# rev3_01.net
KiCad netlist of a schematic drawn in EAGLE
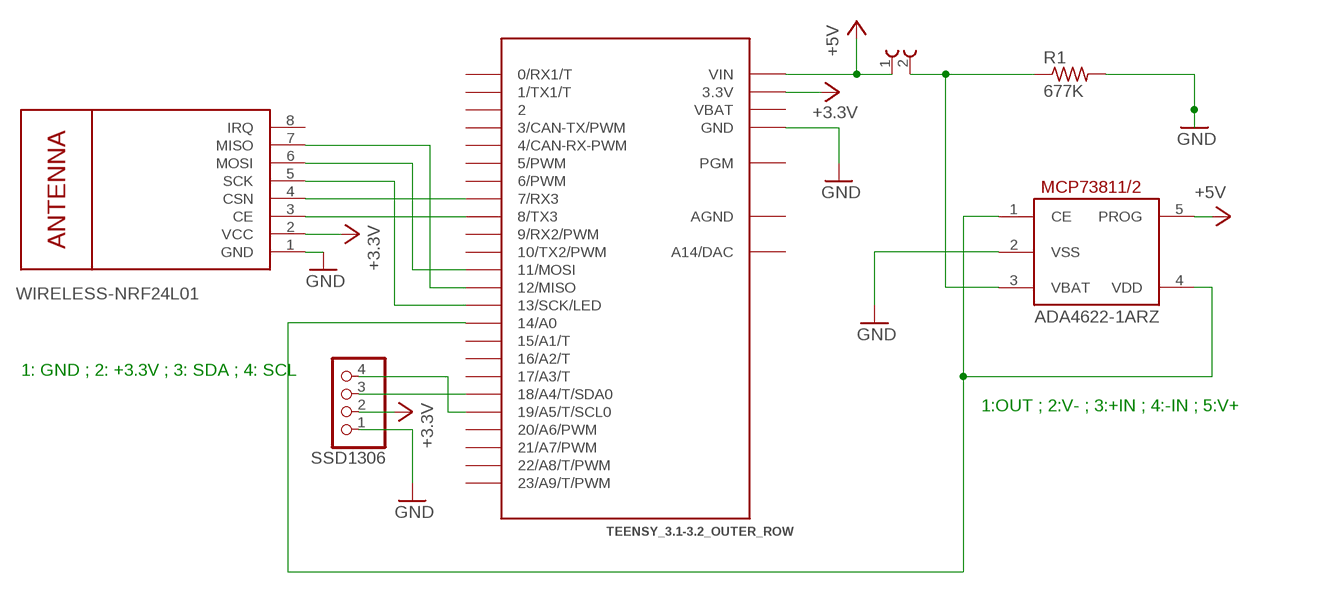
[diagram p0: schematic, sheet 1]

(export (version "E")
  (design (tool "Eeschema 10.0.6"))
  (components
    (comp (ref "ADA4622-1ARZ")
      (value "MCP73811/2")
      (footprint "eagle-import:SOT23-5L")
      (libsource (lib "eagle-import") (part "MCP73811/2"))
    )
    (comp (ref "M1")
      (value "WIRELESS-NRF24L01")
      (footprint "eagle-import:WIRELESS-NRF24L01")
      (libsource (lib "eagle-import") (part "WIRELESS-NRF24L01"))
    )
    (comp (ref "R1")
      (value "677K")
      (footprint "eagle-import:R0805W")
      (libsource (lib "eagle-import") (part "R-US_R0805W"))
    )
    (comp (ref "R_MES")
      (value "691214310002")
      (footprint "eagle-import:691214310002")
      (libsource (lib "eagle-import") (part "691214310002"))
    )
    (comp (ref "SSD1306")
      (value "PINHD-1X4")
      (footprint "eagle-import:1X04")
      (libsource (lib "eagle-import") (part "PINHD-1X4"))
    )
    (comp (ref "U$2")
      (value "TEENSY_3.1-3.2_OUTER_ROW")
      (footprint "eagle-import:TEENSY_3.0-3.2&LC_OUTER_ROW")
      (libsource (lib "eagle-import") (part "TEENSY_3.1-3.2_OUTER_ROW"))
    )
  )
  (nets
    (net (code "1") (name "+3.3V") (class "Default")
      (node (ref "M1") (pin "2") (pinfunction "VCC_2") (pintype "power_in"))
      (node (ref "SSD1306") (pin "2") (pinfunction "2_2") (pintype "passive"))
      (node (ref "U$2") (pin "3.3V") (pinfunction "3.3V_3.3V") (pintype "power_in"))
      (node (ref "U$2") (pin "3.3V1") (pinfunction "3.3V_3.3V1") (pintype "power_in"))
    )
    (net (code "2") (name "+5V") (class "Default")
      (node (ref "ADA4622-1ARZ") (pin "5") (pinfunction "PROG_5") (pintype "input"))
      (node (ref "R_MES") (pin "1") (pinfunction "1_1") (pintype "passive"))
      (node (ref "U$2") (pin "VIN") (pinfunction "VIN_VIN") (pintype "power_in"))
    )
    (net (code "3") (name "/AGND") (class "Default")
      (node (ref "U$2") (pin "AGND") (pinfunction "AGND_AGND") (pintype "power_in"))
    )
    (net (code "4") (name "/VBAT") (class "Default")
      (node (ref "U$2") (pin "VBAT") (pinfunction "VBAT_VBAT") (pintype "power_in"))
    )
    (net (code "5") (name "GND") (class "Default")
      (node (ref "ADA4622-1ARZ") (pin "2") (pinfunction "VSS_2") (pintype "power_in"))
      (node (ref "M1") (pin "1") (pinfunction "GND_1") (pintype "power_in"))
      (node (ref "R1") (pin "2") (pinfunction "2_2") (pintype "passive"))
      (node (ref "SSD1306") (pin "1") (pinfunction "1_1") (pintype "passive"))
      (node (ref "U$2") (pin "GND") (pinfunction "GND_GND") (pintype "power_in"))
      (node (ref "U$2") (pin "GND1") (pinfunction "GND_GND1") (pintype "power_in"))
    )
    (net (code "6") (name "Net-(ADA4622-1ARZ-CE)") (class "Default")
      (node (ref "ADA4622-1ARZ") (pin "1") (pinfunction "CE_1") (pintype "input"))
      (node (ref "ADA4622-1ARZ") (pin "4") (pinfunction "VDD_4") (pintype "power_in"))
      (node (ref "U$2") (pin "14/A0") (pinfunction "14/A0_14/A0") (pintype "bidirectional"))
    )
    (net (code "7") (name "Net-(ADA4622-1ARZ-VBAT)") (class "Default")
      (node (ref "ADA4622-1ARZ") (pin "3") (pinfunction "VBAT_3") (pintype "bidirectional"))
      (node (ref "R1") (pin "1") (pinfunction "1_1") (pintype "passive"))
      (node (ref "R_MES") (pin "2") (pinfunction "2_2") (pintype "passive"))
    )
    (net (code "8") (name "Net-(M1-CE)") (class "Default")
      (node (ref "M1") (pin "3") (pinfunction "CE_3") (pintype "bidirectional"))
      (node (ref "U$2") (pin "8") (pinfunction "8/TX3_8") (pintype "bidirectional"))
    )
    (net (code "9") (name "Net-(M1-CSN)") (class "Default")
      (node (ref "M1") (pin "4") (pinfunction "CSN_4") (pintype "bidirectional"))
      (node (ref "U$2") (pin "7") (pinfunction "7/RX3_7") (pintype "bidirectional"))
    )
    (net (code "10") (name "Net-(M1-MISO)") (class "Default")
      (node (ref "M1") (pin "7") (pinfunction "MISO_7") (pintype "bidirectional"))
      (node (ref "U$2") (pin "12") (pinfunction "12/MISO_12") (pintype "bidirectional"))
    )
    (net (code "11") (name "Net-(M1-MOSI)") (class "Default")
      (node (ref "M1") (pin "6") (pinfunction "MOSI_6") (pintype "bidirectional"))
      (node (ref "U$2") (pin "11") (pinfunction "11/MOSI_11") (pintype "bidirectional"))
    )
    (net (code "12") (name "Net-(M1-SCK)") (class "Default")
      (node (ref "M1") (pin "5") (pinfunction "SCK_5") (pintype "bidirectional"))
      (node (ref "U$2") (pin "13") (pinfunction "13/SCK/LED_13") (pintype "bidirectional"))
    )
    (net (code "13") (name "Net-(U$2-18{slash}A4{slash}T{slash}SDA0)") (class "Default")
      (node (ref "SSD1306") (pin "3") (pinfunction "3_3") (pintype "passive"))
      (node (ref "U$2") (pin "18/A4") (pinfunction "18/A4/T/SDA0_18/A4") (pintype "bidirectional"))
    )
    (net (code "14") (name "Net-(U$2-19{slash}A5{slash}T{slash}SCL0)") (class "Default")
      (node (ref "SSD1306") (pin "4") (pinfunction "4_4") (pintype "passive"))
      (node (ref "U$2") (pin "19/A5") (pinfunction "19/A5/T/SCL0_19/A5") (pintype "bidirectional"))
    )
    (net (code "15") (name "unconnected-(M1-IRQ-Pad8)") (class "Default")
      (node (ref "M1") (pin "8") (pinfunction "IRQ_8") (pintype "bidirectional"))
    )
    (net (code "16") (name "unconnected-(U$2-0{slash}RX1{slash}T-Pad0)") (class "Default")
      (node (ref "U$2") (pin "0") (pinfunction "0/RX1/T_0") (pintype "bidirectional"))
    )
    (net (code "17") (name "unconnected-(U$2-1{slash}TX1{slash}T-Pad1)") (class "Default")
      (node (ref "U$2") (pin "1") (pinfunction "1/TX1/T_1") (pintype "bidirectional"))
    )
    (net (code "18") (name "unconnected-(U$2-3{slash}CAN-TX{slash}PWM-Pad3)") (class "Default")
      (node (ref "U$2") (pin "3") (pinfunction "3/CAN-TX/PWM_3") (pintype "bidirectional"))
    )
    (net (code "19") (name "unconnected-(U$2-4{slash}CAN-RX-PWM-Pad4)") (class "Default")
      (node (ref "U$2") (pin "4") (pinfunction "4/CAN-RX-PWM_4") (pintype "bidirectional"))
    )
    (net (code "20") (name "unconnected-(U$2-5{slash}PWM-Pad5)") (class "Default")
      (node (ref "U$2") (pin "5") (pinfunction "5/PWM_5") (pintype "bidirectional"))
    )
    (net (code "21") (name "unconnected-(U$2-6{slash}PWM-Pad6)") (class "Default")
      (node (ref "U$2") (pin "6") (pinfunction "6/PWM_6") (pintype "bidirectional"))
    )
    (net (code "22") (name "unconnected-(U$2-9{slash}RX2{slash}PWM-Pad9)") (class "Default")
      (node (ref "U$2") (pin "9") (pinfunction "9/RX2/PWM_9") (pintype "bidirectional"))
    )
    (net (code "23") (name "unconnected-(U$2-10{slash}TX2{slash}PWM-Pad10)") (class "Default")
      (node (ref "U$2") (pin "10") (pinfunction "10/TX2/PWM_10") (pintype "bidirectional"))
    )
    (net (code "24") (name "unconnected-(U$2-15{slash}A1{slash}T-Pad15{slash}A1)") (class "Default")
      (node (ref "U$2") (pin "15/A1") (pinfunction "15/A1/T_15/A1") (pintype "bidirectional"))
    )
    (net (code "25") (name "unconnected-(U$2-16{slash}A2{slash}T-Pad16{slash}A2)") (class "Default")
      (node (ref "U$2") (pin "16/A2") (pinfunction "16/A2/T_16/A2") (pintype "bidirectional"))
    )
    (net (code "26") (name "unconnected-(U$2-17{slash}A3{slash}T-Pad17{slash}A3)") (class "Default")
      (node (ref "U$2") (pin "17/A3") (pinfunction "17/A3/T_17/A3") (pintype "bidirectional"))
    )
    (net (code "27") (name "unconnected-(U$2-20{slash}A6{slash}PWM-Pad20{slash}A6)") (class "Default")
      (node (ref "U$2") (pin "20/A6") (pinfunction "20/A6/PWM_20/A6") (pintype "bidirectional"))
    )
    (net (code "28") (name "unconnected-(U$2-21{slash}A7{slash}PWM-Pad21{slash}A7)") (class "Default")
      (node (ref "U$2") (pin "21/A7") (pinfunction "21/A7/PWM_21/A7") (pintype "bidirectional"))
    )
    (net (code "29") (name "unconnected-(U$2-22{slash}A8{slash}T{slash}PWM-Pad22{slash}A8)") (class "Default")
      (node (ref "U$2") (pin "22/A8") (pinfunction "22/A8/T/PWM_22/A8") (pintype "bidirectional"))
    )
    (net (code "30") (name "unconnected-(U$2-23{slash}A9{slash}T{slash}PWM-Pad23{slash}A9)") (class "Default")
      (node (ref "U$2") (pin "23/A9") (pinfunction "23/A9/T/PWM_23/A9") (pintype "bidirectional"))
    )
    (net (code "31") (name "unconnected-(U$2-A14{slash}DAC-PadRESET{slash}DAC)") (class "Default")
      (node (ref "U$2") (pin "RESET/DAC") (pinfunction "A14/DAC_RESET/DAC") (pintype "bidirectional"))
    )
    (net (code "32") (name "unconnected-(U$2-Pad2)") (class "Default")
      (node (ref "U$2") (pin "2") (pinfunction "2_2") (pintype "bidirectional"))
    )
    (net (code "33") (name "unconnected-(U$2-PadPGM)") (class "Default")
      (node (ref "U$2") (pin "PGM") (pinfunction "PGM_PGM") (pintype "bidirectional"))
    )
  )
)
